# TDS.net
KiCad netlist of a schematic drawn in Altium Designer
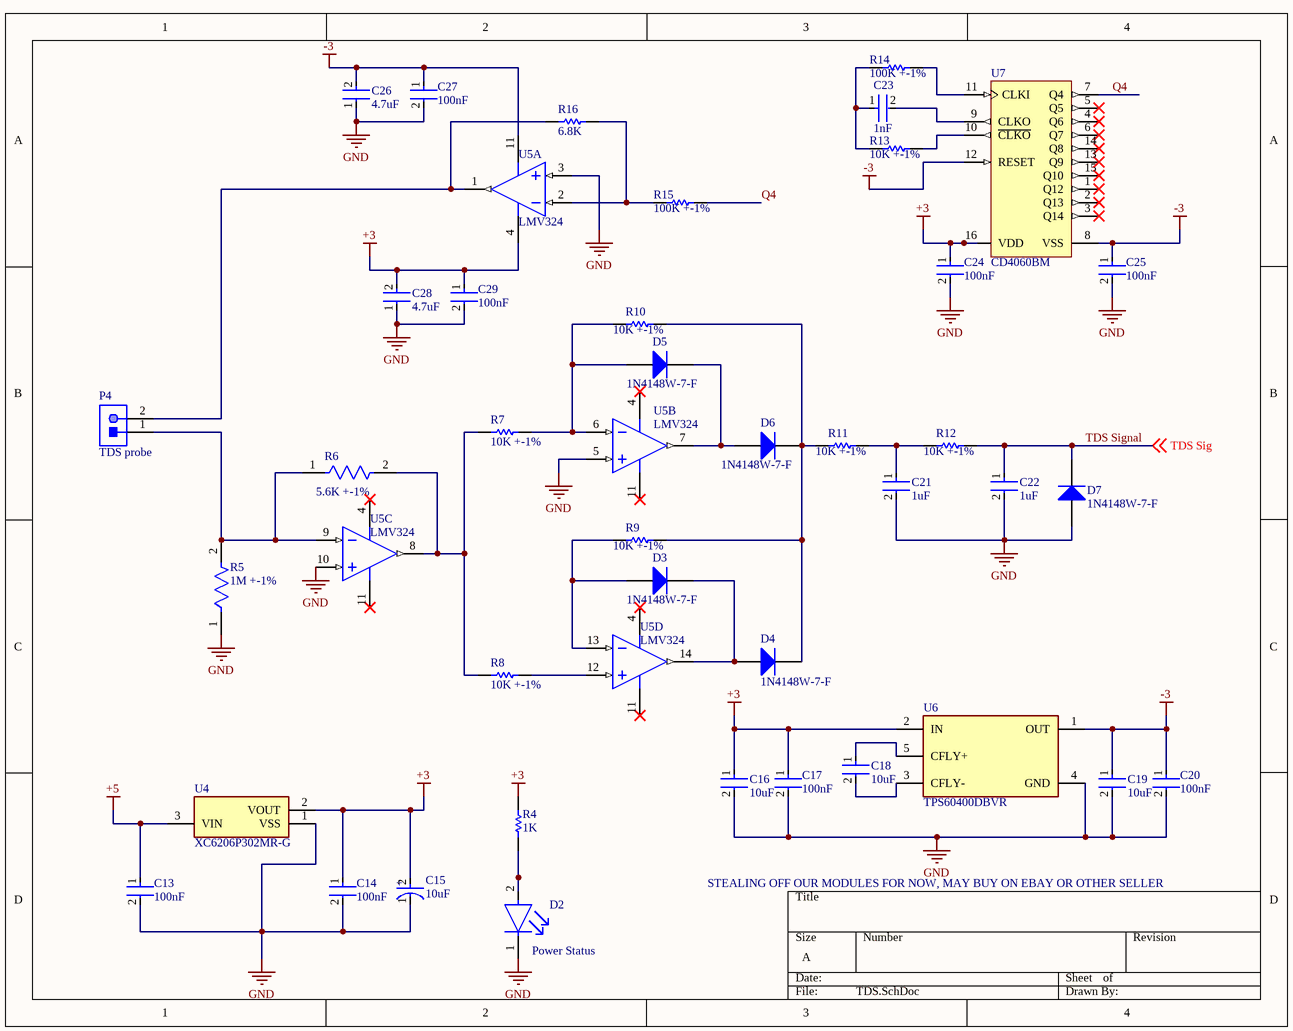
[diagram p0: TDS.SchDoc]

(export (version "E")
  (design (tool "Eeschema 10.0.6"))
  (components
    (comp (ref "C13")
      (value "100nF")
      (footprint "FP-CGA3E-0_3-0_1-IPC_A")
      (description "Cap Ceramic 100nF 50V X7R 10% Pad SMD 0603 +125°C Automotive T/R")
      (fields (field (name "TOLERANCE") "10%") (field (name "VOLTAGE") "50V"))
      (libsource (lib "Altium Content Vault") (part "b4654b650e69147ec39a6b967a45e02"))
    )
    (comp (ref "C14")
      (value "100nF")
      (footprint "FP-CGA3E-0_3-0_1-IPC_A")
      (description "Cap Ceramic 100nF 50V X7R 10% Pad SMD 0603 +125°C Automotive T/R")
      (fields (field (name "TOLERANCE") "10%") (field (name "VOLTAGE") "50V"))
      (libsource (lib "Altium Content Vault") (part "b4654b650e69147ec39a6b967a45e02"))
    )
    (comp (ref "C15")
      (value "10uF")
      (footprint "FP-T491C106K016AT-MFG")
      (description "CAP TANT 10UF 10% 16V 2312")
      (fields (field (name "VOLTAGE") "16V") (field (name "TOLERANCE") "10%"))
      (libsource (lib "Altium Content Vault") (part "a00bbbee19879c290e62620ae7e47b1"))
    )
    (comp (ref "C16")
      (value "10uF")
      (footprint "FP-C0805C-DG-MFG")
      (description "CAP CER 10UF 10V X5R 0805")
      (fields (field (name "TOLERANCE") "10%") (field (name "MANUFACTURER PART NUMBER") "C0805C106K8PACTU"))
      (libsource (lib "Altium Content Vault") (part "11868f565c42a9108669ba33697ecf6"))
    )
    (comp (ref "C17")
      (value "100nF")
      (footprint "FP-CGA3E-0_3-0_1-IPC_A")
      (description "Cap Ceramic 100nF 50V X7R 10% Pad SMD 0603 +125°C Automotive T/R")
      (fields (field (name "TOLERANCE") "10%") (field (name "VOLTAGE") "50V"))
      (libsource (lib "Altium Content Vault") (part "b4654b650e69147ec39a6b967a45e02"))
    )
    (comp (ref "C18")
      (value "10uF")
      (footprint "FP-C0805C-DG-MFG")
      (description "CAP CER 10UF 10V X5R 0805")
      (fields (field (name "TOLERANCE") "10%") (field (name "MANUFACTURER PART NUMBER") "C0805C106K8PACTU"))
      (libsource (lib "Altium Content Vault") (part "11868f565c42a9108669ba33697ecf6"))
    )
    (comp (ref "C19")
      (value "10uF")
      (footprint "FP-C0805C-DG-MFG")
      (description "CAP CER 10UF 10V X5R 0805")
      (fields (field (name "TOLERANCE") "10%") (field (name "MANUFACTURER PART NUMBER") "C0805C106K8PACTU"))
      (libsource (lib "Altium Content Vault") (part "11868f565c42a9108669ba33697ecf6"))
    )
    (comp (ref "C20")
      (value "100nF")
      (footprint "FP-CGA3E-0_3-0_1-IPC_A")
      (description "Cap Ceramic 100nF 50V X7R 10% Pad SMD 0603 +125°C Automotive T/R")
      (fields (field (name "TOLERANCE") "10%") (field (name "VOLTAGE") "50V"))
      (libsource (lib "Altium Content Vault") (part "b4654b650e69147ec39a6b967a45e02"))
    )
    (comp (ref "C21")
      (value "1uF")
      (footprint "FP-0603-L_1_6_0_1-W_0_8_0-IPC_A")
      (description "None")
      (fields (field (name "TOLERANCE") "10%"))
      (libsource (lib "Altium Content Vault") (part "02cd4be3c70576c341d710602a673aa"))
    )
    (comp (ref "C22")
      (value "1uF")
      (footprint "FP-0603-L_1_6_0_1-W_0_8_0-IPC_A")
      (description "None")
      (fields (field (name "TOLERANCE") "10%"))
      (libsource (lib "Altium Content Vault") (part "02cd4be3c70576c341d710602a673aa"))
    )
    (comp (ref "C23")
      (value "1nF")
      (footprint "FP-0603-L_1_6_0_15-W_0_81-IPC_A")
      (description "General Purpose Ceramic Capacitor, 0603, 1nF, 10%, X7R, 15%, 50V")
      (fields (field (name "VOLTAGE") "50V") (field (name "TOLERANCE") "10%"))
      (libsource (lib "Altium Content Vault") (part "02cd4be3c70576c341d710602a673aa"))
    )
    (comp (ref "C24")
      (value "100nF")
      (footprint "FP-CGA3E-0_3-0_1-IPC_A")
      (description "Cap Ceramic 100nF 50V X7R 10% Pad SMD 0603 +125°C Automotive T/R")
      (fields (field (name "TOLERANCE") "10%") (field (name "VOLTAGE") "50V"))
      (libsource (lib "Altium Content Vault") (part "b4654b650e69147ec39a6b967a45e02"))
    )
    (comp (ref "C25")
      (value "100nF")
      (footprint "FP-CGA3E-0_3-0_1-IPC_A")
      (description "Cap Ceramic 100nF 50V X7R 10% Pad SMD 0603 +125°C Automotive T/R")
      (fields (field (name "TOLERANCE") "10%") (field (name "VOLTAGE") "50V"))
      (libsource (lib "Altium Content Vault") (part "b4654b650e69147ec39a6b967a45e02"))
    )
    (comp (ref "C26")
      (value "4.7uF")
      (footprint "FP-GRM188-0_1-MFG")
      (description "CAP CER 4.7UF 6.3V X5R 0603")
      (fields (field (name "VOLTAGE") "6.3V") (field (name "TOLERANCE") "10%"))
      (libsource (lib "Altium Content Vault") (part "236180d848d6139a670b325ea6854c9"))
    )
    (comp (ref "C27")
      (value "100nF")
      (footprint "FP-CGA3E-0_3-0_1-IPC_A")
      (description "Cap Ceramic 100nF 50V X7R 10% Pad SMD 0603 +125°C Automotive T/R")
      (fields (field (name "TOLERANCE") "10%") (field (name "VOLTAGE") "50V"))
      (libsource (lib "Altium Content Vault") (part "b4654b650e69147ec39a6b967a45e02"))
    )
    (comp (ref "C28")
      (value "4.7uF")
      (footprint "FP-GRM188-0_1-MFG")
      (description "CAP CER 4.7UF 6.3V X5R 0603")
      (fields (field (name "VOLTAGE") "6.3V") (field (name "TOLERANCE") "10%"))
      (libsource (lib "Altium Content Vault") (part "236180d848d6139a670b325ea6854c9"))
    )
    (comp (ref "C29")
      (value "100nF")
      (footprint "FP-CGA3E-0_3-0_1-IPC_A")
      (description "Cap Ceramic 100nF 50V X7R 10% Pad SMD 0603 +125°C Automotive T/R")
      (fields (field (name "TOLERANCE") "10%") (field (name "VOLTAGE") "50V"))
      (libsource (lib "Altium Content Vault") (part "b4654b650e69147ec39a6b967a45e02"))
    )
    (comp (ref "D2")
      (value "Power Status")
      (footprint "FP-LTST-C191TBKT-MFG")
      (description "LED BLUE CLEAR CHIP SMD")
      (libsource (lib "Altium Content Vault") (part "8706943c75ba83719d021d2fdc84c58"))
    )
    (comp (ref "D3")
      (value "1N4148W-7-F")
      (footprint "DIOD-SOD123-2_V")
      (description "Fast Switching Diode, 100 V, 0.15 A, -65 to 150 degC, 2-Pin?SOD123, RoHS, Tape and Reel")
      (fields (field (name "MANUFACTURER") "DiodesIncorporated"))
      (libsource (lib "Altium Content Vault") (part "D-AK-2"))
    )
    (comp (ref "D4")
      (value "1N4148W-7-F")
      (footprint "DIOD-SOD123-2_V")
      (description "Fast Switching Diode, 100 V, 0.15 A, -65 to 150 degC, 2-Pin?SOD123, RoHS, Tape and Reel")
      (fields (field (name "MANUFACTURER") "DiodesIncorporated"))
      (libsource (lib "Altium Content Vault") (part "D-AK-2"))
    )
    (comp (ref "D5")
      (value "1N4148W-7-F")
      (footprint "DIOD-SOD123-2_V")
      (description "Fast Switching Diode, 100 V, 0.15 A, -65 to 150 degC, 2-Pin?SOD123, RoHS, Tape and Reel")
      (fields (field (name "MANUFACTURER") "DiodesIncorporated"))
      (libsource (lib "Altium Content Vault") (part "D-AK-2"))
    )
    (comp (ref "D6")
      (value "1N4148W-7-F")
      (footprint "DIOD-SOD123-2_V")
      (description "Fast Switching Diode, 100 V, 0.15 A, -65 to 150 degC, 2-Pin?SOD123, RoHS, Tape and Reel")
      (fields (field (name "MANUFACTURER") "DiodesIncorporated"))
      (libsource (lib "Altium Content Vault") (part "D-AK-2"))
    )
    (comp (ref "D7")
      (value "1N4148W-7-F")
      (footprint "DIOD-SOD123-2_V")
      (description "Fast Switching Diode, 100 V, 0.15 A, -65 to 150 degC, 2-Pin?SOD123, RoHS, Tape and Reel")
      (fields (field (name "MANUFACTURER") "DiodesIncorporated"))
      (libsource (lib "Altium Content Vault") (part "D-AK-2"))
    )
    (comp (ref "P4")
      (value "TDS probe")
      (footprint "JST-S2B-PH-K-S_V")
      (fields (field (name "TOLERANCE") "20%"))
      (libsource (lib "Altium Content Vault") (part "CN-1P-M-R2"))
    )
    (comp (ref "R4")
      (value "1K")
      (footprint "RESC2013X50X30NL20T20")
      (fields (field (name "PART NUMBER") "CRCW08051K00FKEA") (field (name "MANUFACTURER") "Vishay Dale"))
      (libsource (lib "Altium Content Vault") (part "RES"))
    )
    (comp (ref "R5")
      (value "1M +-1%")
      (footprint "FP-CRCW0603-e3-MFG")
      (description "RES Thick Film, 1MΩ, 1%, 0.1W, 100ppm/°C, 0603")
      (fields (field (name "TOLERANCE") "1%"))
      (libsource (lib "Altium Content Vault") (part "1029c3af85768c4190bb7ad29bc67b5"))
    )
    (comp (ref "R6")
      (value "5.6K +-1%")
      (footprint "FP-CRCW0603-e3-MFG")
      (description "RES Thick Film, 5.6kΩ, 1%, 0.1W, 100ppm/°C, 0603")
      (fields (field (name "TOLERANCE") "1%"))
      (libsource (lib "Altium Content Vault") (part "1029c3af85768c4190bb7ad29bc67b5"))
    )
    (comp (ref "R7")
      (value "10K +-1%")
      (footprint "RESC1609X50X30NL8T20")
      (description "Chip Resistor, 10 KOhm, +/- 1%, 100 mW, -55 to 155 degC, 0603 (1608 Metric), RoHS, Tape and Reel")
      (fields (field (name "MANUFACTURER") "Vishay Semiconductor"))
      (libsource (lib "Altium Content Vault") (part "RES-2"))
    )
    (comp (ref "R8")
      (value "10K +-1%")
      (footprint "RESC1609X50X30NL8T20")
      (description "Chip Resistor, 10 KOhm, +/- 1%, 100 mW, -55 to 155 degC, 0603 (1608 Metric), RoHS, Tape and Reel")
      (fields (field (name "MANUFACTURER") "Vishay Semiconductor"))
      (libsource (lib "Altium Content Vault") (part "RES-2"))
    )
    (comp (ref "R9")
      (value "10K +-1%")
      (footprint "RESC1609X50X30NL8T20")
      (description "Chip Resistor, 10 KOhm, +/- 1%, 100 mW, -55 to 155 degC, 0603 (1608 Metric), RoHS, Tape and Reel")
      (fields (field (name "MANUFACTURER") "Vishay Semiconductor"))
      (libsource (lib "Altium Content Vault") (part "RES-2"))
    )
    (comp (ref "R10")
      (value "10K +-1%")
      (footprint "RESC1609X50X30NL8T20")
      (description "Chip Resistor, 10 KOhm, +/- 1%, 100 mW, -55 to 155 degC, 0603 (1608 Metric), RoHS, Tape and Reel")
      (fields (field (name "MANUFACTURER") "Vishay Semiconductor"))
      (libsource (lib "Altium Content Vault") (part "RES-2"))
    )
    (comp (ref "R11")
      (value "10K +-1%")
      (footprint "RESC1609X50X30NL8T20")
      (description "Chip Resistor, 10 KOhm, +/- 1%, 100 mW, -55 to 155 degC, 0603 (1608 Metric), RoHS, Tape and Reel")
      (fields (field (name "MANUFACTURER") "Vishay Semiconductor"))
      (libsource (lib "Altium Content Vault") (part "RES-2"))
    )
    (comp (ref "R12")
      (value "10K +-1%")
      (footprint "RESC1609X50X30NL8T20")
      (description "Chip Resistor, 10 KOhm, +/- 1%, 100 mW, -55 to 155 degC, 0603 (1608 Metric), RoHS, Tape and Reel")
      (fields (field (name "MANUFACTURER") "Vishay Semiconductor"))
      (libsource (lib "Altium Content Vault") (part "RES-2"))
    )
    (comp (ref "R13")
      (value "10K +-1%")
      (footprint "RESC1609X50X30NL8T20")
      (description "Chip Resistor, 10 KOhm, +/- 1%, 100 mW, -55 to 155 degC, 0603 (1608 Metric), RoHS, Tape and Reel")
      (fields (field (name "MANUFACTURER") "Vishay Semiconductor"))
      (libsource (lib "Altium Content Vault") (part "RES-2"))
    )
    (comp (ref "R14")
      (value "100K +-1%")
      (footprint "RESC1608X55X30ML20T20")
      (fields (field (name "PART NUMBER") "ERA3AEB104V") (field (name "MANUFACTURER") "Panasonic"))
      (libsource (lib "Altium Content Vault") (part "RES"))
    )
    (comp (ref "R15")
      (value "100K +-1%")
      (footprint "RESC1608X55X30ML20T20")
      (fields (field (name "PART NUMBER") "ERA3AEB104V") (field (name "MANUFACTURER") "Panasonic"))
      (libsource (lib "Altium Content Vault") (part "RES"))
    )
    (comp (ref "R16")
      (value "6.8K")
      (footprint "RESC1609X50X30LL10T20")
      (fields (field (name "PART NUMBER") "CRCW06036K80FKEA") (field (name "MANUFACTURER") "Vishay Dale"))
      (libsource (lib "Altium Content Vault") (part "RES"))
    )
    (comp (ref "U4")
      (value "XC6206P302MR-G")
      (footprint "SamacSys:SOT95P280X130-3N")
      (description "Integrated Circuit")
      (fields (field (name "MOUSER PART NUMBER") "865-XC6206P302MR-G"))
      (libsource (lib "SamacSys") (part "XC6206P302MR-G"))
    )
    (comp (ref "U5")
      (value "LMV324")
      (footprint "D0014A_V")
      (libsource (lib "Altium Content Vault") (part "TI-LMV324-D-14"))
    )
    (comp (ref "U6")
      (value "TPS60400DBVR")
      (footprint "FP-DBV0005A-IPC_B")
      (description "IC REG CHARG PUMP INV 60MA SOT23")
      (libsource (lib "Altium Content Vault") (part "027376aeb0d6df1338393bd3c828556"))
    )
    (comp (ref "U7")
      (value "CD4060BM")
      (footprint "D0016A_M")
      (fields (field (name "MANUFACTURER") "Texas Instruments"))
      (libsource (lib "Altium Content Vault") (part "TI-CD4060B-16"))
    )
  )
  (nets
    (net (code "1") (name "+3") (class "Default")
      (node (ref "C14") (pin "1") (pinfunction "1_1") (pintype "passive"))
      (node (ref "C15") (pin "2") (pinfunction "A_2") (pintype "passive"))
      (node (ref "C16") (pin "1") (pinfunction "1_1") (pintype "passive"))
      (node (ref "C17") (pin "1") (pinfunction "1_1") (pintype "passive"))
      (node (ref "C24") (pin "1") (pinfunction "1_1") (pintype "passive"))
      (node (ref "C28") (pin "2") (pinfunction "2_2") (pintype "passive"))
      (node (ref "C29") (pin "1") (pinfunction "1_1") (pintype "passive"))
      (node (ref "R4") (pin "2") (pinfunction "2_2") (pintype "passive"))
      (node (ref "U4") (pin "2") (pinfunction "VOUT_2") (pintype "passive"))
      (node (ref "U5") (pin "4") (pinfunction "VCC+_4") (pintype "power_in"))
      (node (ref "U6") (pin "2") (pinfunction "IN_2") (pintype "power_in"))
      (node (ref "U7") (pin "16") (pinfunction "VDD_16") (pintype "power_in"))
    )
    (net (code "2") (name "+5") (class "Default")
      (node (ref "C13") (pin "1") (pinfunction "1_1") (pintype "passive"))
      (node (ref "U4") (pin "3") (pinfunction "VIN_3") (pintype "passive"))
    )
    (net (code "3") (name "-3") (class "Default")
      (node (ref "C19") (pin "1") (pinfunction "1_1") (pintype "passive"))
      (node (ref "C20") (pin "1") (pinfunction "1_1") (pintype "passive"))
      (node (ref "C25") (pin "1") (pinfunction "1_1") (pintype "passive"))
      (node (ref "C26") (pin "2") (pinfunction "2_2") (pintype "passive"))
      (node (ref "C27") (pin "1") (pinfunction "1_1") (pintype "passive"))
      (node (ref "U5") (pin "11") (pinfunction "GND_11") (pintype "power_in"))
      (node (ref "U6") (pin "1") (pinfunction "OUT_1") (pintype "power_in"))
      (node (ref "U7") (pin "12") (pinfunction "RESET_12") (pintype "input"))
      (node (ref "U7") (pin "8") (pinfunction "VSS_8") (pintype "power_in"))
    )
    (net (code "4") (name "/Q4") (class "Default")
      (node (ref "R15") (pin "2") (pinfunction "2_2") (pintype "passive"))
      (node (ref "U7") (pin "7") (pinfunction "Q4_7") (pintype "output"))
    )
    (net (code "5") (name "GND") (class "Default")
      (node (ref "C13") (pin "2") (pinfunction "2_2") (pintype "passive"))
      (node (ref "C14") (pin "2") (pinfunction "2_2") (pintype "passive"))
      (node (ref "C15") (pin "1") (pinfunction "C_1") (pintype "passive"))
      (node (ref "C16") (pin "2") (pinfunction "2_2") (pintype "passive"))
      (node (ref "C17") (pin "2") (pinfunction "2_2") (pintype "passive"))
      (node (ref "C19") (pin "2") (pinfunction "2_2") (pintype "passive"))
      (node (ref "C20") (pin "2") (pinfunction "2_2") (pintype "passive"))
      (node (ref "C21") (pin "2") (pinfunction "2_2") (pintype "passive"))
      (node (ref "C22") (pin "2") (pinfunction "2_2") (pintype "passive"))
      (node (ref "C24") (pin "2") (pinfunction "2_2") (pintype "passive"))
      (node (ref "C25") (pin "2") (pinfunction "2_2") (pintype "passive"))
      (node (ref "C26") (pin "1") (pinfunction "1_1") (pintype "passive"))
      (node (ref "C27") (pin "2") (pinfunction "2_2") (pintype "passive"))
      (node (ref "C28") (pin "1") (pinfunction "1_1") (pintype "passive"))
      (node (ref "C29") (pin "2") (pinfunction "2_2") (pintype "passive"))
      (node (ref "D2") (pin "1") (pinfunction "C_1") (pintype "passive"))
      (node (ref "D7") (pin "1") (pinfunction "A_1") (pintype "passive"))
      (node (ref "R5") (pin "1") (pinfunction "1_1") (pintype "passive"))
      (node (ref "U4") (pin "1") (pinfunction "VSS_1") (pintype "passive"))
      (node (ref "U5") (pin "10") (pinfunction "3IN+_10") (pintype "input"))
      (node (ref "U5") (pin "3") (pinfunction "1IN+_3") (pintype "input"))
      (node (ref "U5") (pin "5") (pinfunction "2IN+_5") (pintype "input"))
      (node (ref "U6") (pin "4") (pinfunction "GND_4") (pintype "power_in"))
    )
    (net (code "6") (name "Net-(C21-Pad1)") (class "Default")
      (node (ref "C21") (pin "1") (pinfunction "1_1") (pintype "passive"))
      (node (ref "R11") (pin "2") (pinfunction "2_2") (pintype "passive"))
      (node (ref "R12") (pin "1") (pinfunction "1_1") (pintype "passive"))
    )
    (net (code "7") (name "Net-(C23-Pad1)") (class "Default")
      (node (ref "C23") (pin "1") (pinfunction "1_1") (pintype "passive"))
      (node (ref "R13") (pin "1") (pinfunction "1_1") (pintype "passive"))
      (node (ref "R14") (pin "1") (pinfunction "1_1") (pintype "passive"))
    )
    (net (code "8") (name "Net-(D2-A)") (class "Default")
      (node (ref "D2") (pin "2") (pinfunction "A_2") (pintype "passive"))
      (node (ref "R4") (pin "1") (pinfunction "1_1") (pintype "passive"))
    )
    (net (code "9") (name "Net-(D3-A)") (class "Default")
      (node (ref "D3") (pin "1") (pinfunction "A_1") (pintype "passive"))
      (node (ref "R9") (pin "1") (pinfunction "1_1") (pintype "passive"))
      (node (ref "U5") (pin "13") (pinfunction "4IN-_13") (pintype "input"))
    )
    (net (code "10") (name "Net-(D3-K)") (class "Default")
      (node (ref "D3") (pin "2") (pinfunction "K_2") (pintype "passive"))
      (node (ref "D4") (pin "1") (pinfunction "A_1") (pintype "passive"))
      (node (ref "U5") (pin "14") (pinfunction "4OUT_14") (pintype "output"))
    )
    (net (code "11") (name "Net-(D4-K)") (class "Default")
      (node (ref "D4") (pin "2") (pinfunction "K_2") (pintype "passive"))
      (node (ref "D6") (pin "2") (pinfunction "K_2") (pintype "passive"))
      (node (ref "R10") (pin "2") (pinfunction "2_2") (pintype "passive"))
      (node (ref "R11") (pin "1") (pinfunction "1_1") (pintype "passive"))
      (node (ref "R9") (pin "2") (pinfunction "2_2") (pintype "passive"))
    )
    (net (code "12") (name "Net-(D5-A)") (class "Default")
      (node (ref "D5") (pin "1") (pinfunction "A_1") (pintype "passive"))
      (node (ref "R10") (pin "1") (pinfunction "1_1") (pintype "passive"))
      (node (ref "R7") (pin "2") (pinfunction "2_2") (pintype "passive"))
      (node (ref "U5") (pin "6") (pinfunction "2IN-_6") (pintype "input"))
    )
    (net (code "13") (name "Net-(D5-K)") (class "Default")
      (node (ref "D5") (pin "2") (pinfunction "K_2") (pintype "passive"))
      (node (ref "D6") (pin "1") (pinfunction "A_1") (pintype "passive"))
      (node (ref "U5") (pin "7") (pinfunction "2OUT_7") (pintype "output"))
    )
    (net (code "14") (name "Net-(U5A-1IN-)") (class "Default")
      (node (ref "R15") (pin "1") (pinfunction "1_1") (pintype "passive"))
      (node (ref "R16") (pin "2") (pinfunction "2_2") (pintype "passive"))
      (node (ref "U5") (pin "2") (pinfunction "1IN-_2") (pintype "input"))
    )
    (net (code "15") (name "Net-(U5A-1OUT)") (class "Default")
      (node (ref "P4") (pin "2") (pinfunction "2_2") (pintype "passive"))
      (node (ref "R16") (pin "1") (pinfunction "1_1") (pintype "passive"))
      (node (ref "U5") (pin "1") (pinfunction "1OUT_1") (pintype "output"))
    )
    (net (code "16") (name "Net-(U5C-3IN-)") (class "Default")
      (node (ref "P4") (pin "1") (pinfunction "1_1") (pintype "passive"))
      (node (ref "R5") (pin "2") (pinfunction "2_2") (pintype "passive"))
      (node (ref "R6") (pin "1") (pinfunction "1_1") (pintype "passive"))
      (node (ref "U5") (pin "9") (pinfunction "3IN-_9") (pintype "input"))
    )
    (net (code "17") (name "Net-(U5C-3OUT)") (class "Default")
      (node (ref "R6") (pin "2") (pinfunction "2_2") (pintype "passive"))
      (node (ref "R7") (pin "1") (pinfunction "1_1") (pintype "passive"))
      (node (ref "R8") (pin "1") (pinfunction "1_1") (pintype "passive"))
      (node (ref "U5") (pin "8") (pinfunction "3OUT_8") (pintype "output"))
    )
    (net (code "18") (name "Net-(U5D-4IN+)") (class "Default")
      (node (ref "R8") (pin "2") (pinfunction "2_2") (pintype "passive"))
      (node (ref "U5") (pin "12") (pinfunction "4IN+_12") (pintype "input"))
    )
    (net (code "19") (name "Net-(U6-CFLY+)") (class "Default")
      (node (ref "C18") (pin "1") (pinfunction "1_1") (pintype "passive"))
      (node (ref "U6") (pin "5") (pinfunction "CFLY+_5") (pintype "passive"))
    )
    (net (code "20") (name "Net-(U6-CFLY-)") (class "Default")
      (node (ref "C18") (pin "2") (pinfunction "2_2") (pintype "passive"))
      (node (ref "U6") (pin "3") (pinfunction "CFLY-_3") (pintype "passive"))
    )
    (net (code "21") (name "Net-(U7-CLKI)") (class "Default")
      (node (ref "R14") (pin "2") (pinfunction "2_2") (pintype "passive"))
      (node (ref "U7") (pin "11") (pinfunction "CLKI_11") (pintype "input"))
    )
    (net (code "22") (name "Net-(U7-CLKO)") (class "Default")
      (node (ref "C23") (pin "2") (pinfunction "2_2") (pintype "passive"))
      (node (ref "U7") (pin "9") (pinfunction "CLKO_9") (pintype "output"))
    )
    (net (code "23") (name "Net-(U7-~{CLKO})") (class "Default")
      (node (ref "R13") (pin "2") (pinfunction "2_2") (pintype "passive"))
      (node (ref "U7") (pin "10") (pinfunction "~{CLKO}_10") (pintype "output"))
    )
    (net (code "24") (name "TDS Sig") (class "Default")
      (node (ref "C22") (pin "1") (pinfunction "1_1") (pintype "passive"))
      (node (ref "D7") (pin "2") (pinfunction "K_2") (pintype "passive"))
      (node (ref "R12") (pin "2") (pinfunction "2_2") (pintype "passive"))
    )
    (net (code "25") (name "unconnected-(U5B-GND-Pad11)") (class "Default")
      (node (ref "U5") (pin "11") (pinfunction "GND_11") (pintype "power_in+no_connect"))
    )
    (net (code "26") (name "unconnected-(U5B-VCC+-Pad4)") (class "Default")
      (node (ref "U5") (pin "4") (pinfunction "VCC+_4") (pintype "power_in+no_connect"))
    )
    (net (code "27") (name "unconnected-(U5C-GND-Pad11)") (class "Default")
      (node (ref "U5") (pin "11") (pinfunction "GND_11") (pintype "power_in+no_connect"))
    )
    (net (code "28") (name "unconnected-(U5C-VCC+-Pad4)") (class "Default")
      (node (ref "U5") (pin "4") (pinfunction "VCC+_4") (pintype "power_in+no_connect"))
    )
    (net (code "29") (name "unconnected-(U5D-GND-Pad11)") (class "Default")
      (node (ref "U5") (pin "11") (pinfunction "GND_11") (pintype "power_in+no_connect"))
    )
    (net (code "30") (name "unconnected-(U5D-VCC+-Pad4)") (class "Default")
      (node (ref "U5") (pin "4") (pinfunction "VCC+_4") (pintype "power_in+no_connect"))
    )
    (net (code "31") (name "unconnected-(U7-Q5-Pad5)") (class "Default")
      (node (ref "U7") (pin "5") (pinfunction "Q5_5") (pintype "output+no_connect"))
    )
    (net (code "32") (name "unconnected-(U7-Q6-Pad4)") (class "Default")
      (node (ref "U7") (pin "4") (pinfunction "Q6_4") (pintype "output+no_connect"))
    )
    (net (code "33") (name "unconnected-(U7-Q7-Pad6)") (class "Default")
      (node (ref "U7") (pin "6") (pinfunction "Q7_6") (pintype "output+no_connect"))
    )
    (net (code "34") (name "unconnected-(U7-Q8-Pad14)") (class "Default")
      (node (ref "U7") (pin "14") (pinfunction "Q8_14") (pintype "output+no_connect"))
    )
    (net (code "35") (name "unconnected-(U7-Q9-Pad13)") (class "Default")
      (node (ref "U7") (pin "13") (pinfunction "Q9_13") (pintype "output+no_connect"))
    )
    (net (code "36") (name "unconnected-(U7-Q10-Pad15)") (class "Default")
      (node (ref "U7") (pin "15") (pinfunction "Q10_15") (pintype "output+no_connect"))
    )
    (net (code "37") (name "unconnected-(U7-Q12-Pad1)") (class "Default")
      (node (ref "U7") (pin "1") (pinfunction "Q12_1") (pintype "output+no_connect"))
    )
    (net (code "38") (name "unconnected-(U7-Q13-Pad2)") (class "Default")
      (node (ref "U7") (pin "2") (pinfunction "Q13_2") (pintype "output+no_connect"))
    )
    (net (code "39") (name "unconnected-(U7-Q14-Pad3)") (class "Default")
      (node (ref "U7") (pin "3") (pinfunction "Q14_3") (pintype "output+no_connect"))
    )
  )
)
